# meter.net
KiCad netlist of a schematic drawn in EAGLE
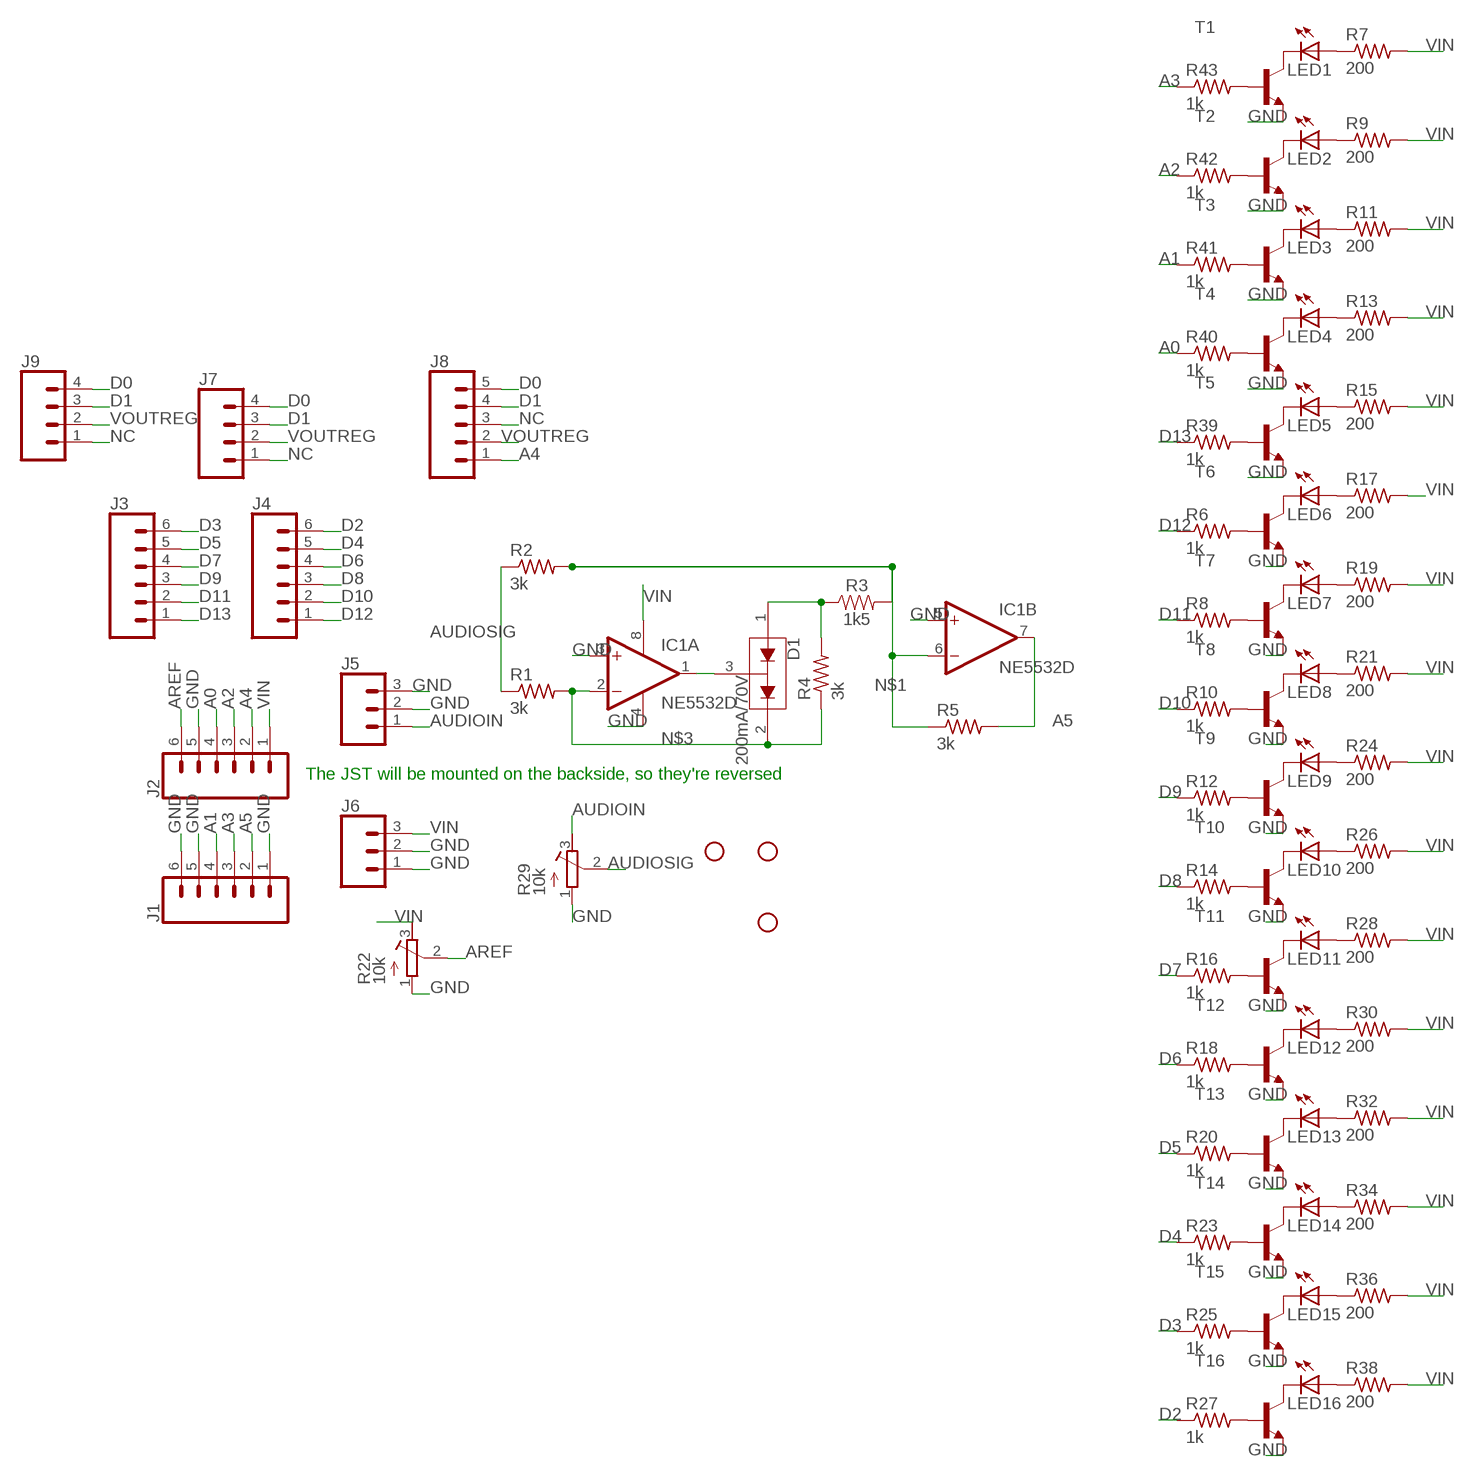
[diagram p0: schematic, sheet 1]

(export (version "E")
  (design (tool "Eeschema 10.0.6"))
  (components
    (comp (ref "D1")
      (value "200mA/70V")
      (footprint "eagle-import:SOT23-3")
      (libsource (lib "eagle-import") (part "BAV99"))
    )
    (comp (ref "H1")
      (value "STAND-OFF")
      (footprint "eagle-import:STAND-OFF")
      (libsource (lib "eagle-import") (part "STAND-OFF"))
    )
    (comp (ref "H2")
      (value "STAND-OFF")
      (footprint "eagle-import:STAND-OFF")
      (libsource (lib "eagle-import") (part "STAND-OFF"))
    )
    (comp (ref "H4")
      (value "STAND-OFF")
      (footprint "eagle-import:STAND-OFF")
      (libsource (lib "eagle-import") (part "STAND-OFF"))
    )
    (comp (ref "IC1")
      (value "NE5532D")
      (footprint "eagle-import:SO08")
      (libsource (lib "eagle-import") (part "NE5532D"))
    )
    (comp (ref "J1")
      (value "CONN_061.27MM")
      (footprint "eagle-import:1X06_1.27MM")
      (libsource (lib "eagle-import") (part "CONN_061.27MM"))
    )
    (comp (ref "J2")
      (value "CONN_061.27MM")
      (footprint "eagle-import:1X06_1.27MM")
      (libsource (lib "eagle-import") (part "CONN_061.27MM"))
    )
    (comp (ref "J3")
      (value "CONN_061.27MM")
      (footprint "eagle-import:1X06_1.27MM")
      (libsource (lib "eagle-import") (part "CONN_061.27MM"))
    )
    (comp (ref "J4")
      (value "CONN_061.27MM")
      (footprint "eagle-import:1X06_1.27MM")
      (libsource (lib "eagle-import") (part "CONN_061.27MM"))
    )
    (comp (ref "J5")
      (value "CONN_03JST-PTH-VERT")
      (footprint "eagle-import:JST-3-PTH-VERT")
      (libsource (lib "eagle-import") (part "CONN_03JST-PTH-VERT"))
    )
    (comp (ref "J6")
      (value "CONN_03JST-PTH-VERT")
      (footprint "eagle-import:JST-3-PTH-VERT")
      (libsource (lib "eagle-import") (part "CONN_03JST-PTH-VERT"))
    )
    (comp (ref "J7")
      (value "CONN_041.27MM")
      (footprint "eagle-import:1X04_1.27MM")
      (libsource (lib "eagle-import") (part "CONN_041.27MM"))
    )
    (comp (ref "J8")
      (value "CONN_05NO_SILK")
      (footprint "eagle-import:1X05_NO_SILK")
      (libsource (lib "eagle-import") (part "CONN_05NO_SILK"))
    )
    (comp (ref "J9")
      (value "CONN_041.27MM")
      (footprint "eagle-import:1X04_1.27MM")
      (libsource (lib "eagle-import") (part "CONN_041.27MM"))
    )
    (comp (ref "LED1")
      (value "LEDCHIP-LED0805")
      (footprint "eagle-import:CHIP-LED0805")
      (libsource (lib "eagle-import") (part "LEDCHIP-LED0805"))
    )
    (comp (ref "LED2")
      (value "LEDCHIP-LED0805")
      (footprint "eagle-import:CHIP-LED0805")
      (libsource (lib "eagle-import") (part "LEDCHIP-LED0805"))
    )
    (comp (ref "LED3")
      (value "LEDCHIP-LED0805")
      (footprint "eagle-import:CHIP-LED0805")
      (libsource (lib "eagle-import") (part "LEDCHIP-LED0805"))
    )
    (comp (ref "LED4")
      (value "LEDCHIP-LED0805")
      (footprint "eagle-import:CHIP-LED0805")
      (libsource (lib "eagle-import") (part "LEDCHIP-LED0805"))
    )
    (comp (ref "LED5")
      (value "LEDCHIP-LED0805")
      (footprint "eagle-import:CHIP-LED0805")
      (libsource (lib "eagle-import") (part "LEDCHIP-LED0805"))
    )
    (comp (ref "LED6")
      (value "LEDCHIP-LED0805")
      (footprint "eagle-import:CHIP-LED0805")
      (libsource (lib "eagle-import") (part "LEDCHIP-LED0805"))
    )
    (comp (ref "LED7")
      (value "LEDCHIP-LED0805")
      (footprint "eagle-import:CHIP-LED0805")
      (libsource (lib "eagle-import") (part "LEDCHIP-LED0805"))
    )
    (comp (ref "LED8")
      (value "LEDCHIP-LED0805")
      (footprint "eagle-import:CHIP-LED0805")
      (libsource (lib "eagle-import") (part "LEDCHIP-LED0805"))
    )
    (comp (ref "LED9")
      (value "LEDCHIP-LED0805")
      (footprint "eagle-import:CHIP-LED0805")
      (libsource (lib "eagle-import") (part "LEDCHIP-LED0805"))
    )
    (comp (ref "LED10")
      (value "LEDCHIP-LED0805")
      (footprint "eagle-import:CHIP-LED0805")
      (libsource (lib "eagle-import") (part "LEDCHIP-LED0805"))
    )
    (comp (ref "LED11")
      (value "LEDCHIP-LED0805")
      (footprint "eagle-import:CHIP-LED0805")
      (libsource (lib "eagle-import") (part "LEDCHIP-LED0805"))
    )
    (comp (ref "LED12")
      (value "LEDCHIP-LED0805")
      (footprint "eagle-import:CHIP-LED0805")
      (libsource (lib "eagle-import") (part "LEDCHIP-LED0805"))
    )
    (comp (ref "LED13")
      (value "LEDCHIP-LED0805")
      (footprint "eagle-import:CHIP-LED0805")
      (libsource (lib "eagle-import") (part "LEDCHIP-LED0805"))
    )
    (comp (ref "LED14")
      (value "LEDCHIP-LED0805")
      (footprint "eagle-import:CHIP-LED0805")
      (libsource (lib "eagle-import") (part "LEDCHIP-LED0805"))
    )
    (comp (ref "LED15")
      (value "LEDCHIP-LED0805")
      (footprint "eagle-import:CHIP-LED0805")
      (libsource (lib "eagle-import") (part "LEDCHIP-LED0805"))
    )
    (comp (ref "LED16")
      (value "LEDCHIP-LED0805")
      (footprint "eagle-import:CHIP-LED0805")
      (libsource (lib "eagle-import") (part "LEDCHIP-LED0805"))
    )
    (comp (ref "R1")
      (value "3k")
      (footprint "eagle-import:R0805")
      (libsource (lib "eagle-import") (part "R-US_R0805"))
    )
    (comp (ref "R2")
      (value "3k")
      (footprint "eagle-import:R0805")
      (libsource (lib "eagle-import") (part "R-US_R0805"))
    )
    (comp (ref "R3")
      (value "1k5")
      (footprint "eagle-import:1206")
      (libsource (lib "eagle-import") (part "RESISTOR1206"))
    )
    (comp (ref "R4")
      (value "3k")
      (footprint "eagle-import:R0805")
      (libsource (lib "eagle-import") (part "R-US_R0805"))
    )
    (comp (ref "R5")
      (value "3k")
      (footprint "eagle-import:R0805")
      (libsource (lib "eagle-import") (part "R-US_R0805"))
    )
    (comp (ref "R6")
      (value "1k")
      (footprint "eagle-import:R0805")
      (libsource (lib "eagle-import") (part "R-US_R0805"))
    )
    (comp (ref "R7")
      (value "200")
      (footprint "eagle-import:R0805")
      (libsource (lib "eagle-import") (part "R-US_R0805"))
    )
    (comp (ref "R8")
      (value "1k")
      (footprint "eagle-import:R0805")
      (libsource (lib "eagle-import") (part "R-US_R0805"))
    )
    (comp (ref "R9")
      (value "200")
      (footprint "eagle-import:R0805")
      (libsource (lib "eagle-import") (part "R-US_R0805"))
    )
    (comp (ref "R10")
      (value "1k")
      (footprint "eagle-import:R0805")
      (libsource (lib "eagle-import") (part "R-US_R0805"))
    )
    (comp (ref "R11")
      (value "200")
      (footprint "eagle-import:R0805")
      (libsource (lib "eagle-import") (part "R-US_R0805"))
    )
    (comp (ref "R12")
      (value "1k")
      (footprint "eagle-import:R0805")
      (libsource (lib "eagle-import") (part "R-US_R0805"))
    )
    (comp (ref "R13")
      (value "200")
      (footprint "eagle-import:R0805")
      (libsource (lib "eagle-import") (part "R-US_R0805"))
    )
    (comp (ref "R14")
      (value "1k")
      (footprint "eagle-import:R0805")
      (libsource (lib "eagle-import") (part "R-US_R0805"))
    )
    (comp (ref "R15")
      (value "200")
      (footprint "eagle-import:R0805")
      (libsource (lib "eagle-import") (part "R-US_R0805"))
    )
    (comp (ref "R16")
      (value "1k")
      (footprint "eagle-import:R0805")
      (libsource (lib "eagle-import") (part "R-US_R0805"))
    )
    (comp (ref "R17")
      (value "200")
      (footprint "eagle-import:R0805")
      (libsource (lib "eagle-import") (part "R-US_R0805"))
    )
    (comp (ref "R18")
      (value "1k")
      (footprint "eagle-import:R0805")
      (libsource (lib "eagle-import") (part "R-US_R0805"))
    )
    (comp (ref "R19")
      (value "200")
      (footprint "eagle-import:R0805")
      (libsource (lib "eagle-import") (part "R-US_R0805"))
    )
    (comp (ref "R20")
      (value "1k")
      (footprint "eagle-import:R0805")
      (libsource (lib "eagle-import") (part "R-US_R0805"))
    )
    (comp (ref "R21")
      (value "200")
      (footprint "eagle-import:R0805")
      (libsource (lib "eagle-import") (part "R-US_R0805"))
    )
    (comp (ref "R22")
      (value "10k")
      (footprint "eagle-import:RTRIM3296Y")
      (libsource (lib "eagle-import") (part "R-TRIMM3296Y"))
    )
    (comp (ref "R23")
      (value "1k")
      (footprint "eagle-import:R0805")
      (libsource (lib "eagle-import") (part "R-US_R0805"))
    )
    (comp (ref "R24")
      (value "200")
      (footprint "eagle-import:R0805")
      (libsource (lib "eagle-import") (part "R-US_R0805"))
    )
    (comp (ref "R25")
      (value "1k")
      (footprint "eagle-import:R0805")
      (libsource (lib "eagle-import") (part "R-US_R0805"))
    )
    (comp (ref "R26")
      (value "200")
      (footprint "eagle-import:R0805")
      (libsource (lib "eagle-import") (part "R-US_R0805"))
    )
    (comp (ref "R27")
      (value "1k")
      (footprint "eagle-import:R0805")
      (libsource (lib "eagle-import") (part "R-US_R0805"))
    )
    (comp (ref "R28")
      (value "200")
      (footprint "eagle-import:R0805")
      (libsource (lib "eagle-import") (part "R-US_R0805"))
    )
    (comp (ref "R29")
      (value "10k")
      (footprint "eagle-import:RTRIM3296Y")
      (libsource (lib "eagle-import") (part "R-TRIMM3296Y"))
    )
    (comp (ref "R30")
      (value "200")
      (footprint "eagle-import:R0805")
      (libsource (lib "eagle-import") (part "R-US_R0805"))
    )
    (comp (ref "R32")
      (value "200")
      (footprint "eagle-import:R0805")
      (libsource (lib "eagle-import") (part "R-US_R0805"))
    )
    (comp (ref "R34")
      (value "200")
      (footprint "eagle-import:R0805")
      (libsource (lib "eagle-import") (part "R-US_R0805"))
    )
    (comp (ref "R36")
      (value "200")
      (footprint "eagle-import:R0805")
      (libsource (lib "eagle-import") (part "R-US_R0805"))
    )
    (comp (ref "R38")
      (value "200")
      (footprint "eagle-import:R0805")
      (libsource (lib "eagle-import") (part "R-US_R0805"))
    )
    (comp (ref "R39")
      (value "1k")
      (footprint "eagle-import:R0805")
      (libsource (lib "eagle-import") (part "R-US_R0805"))
    )
    (comp (ref "R40")
      (value "1k")
      (footprint "eagle-import:R0805")
      (libsource (lib "eagle-import") (part "R-US_R0805"))
    )
    (comp (ref "R41")
      (value "1k")
      (footprint "eagle-import:R0805")
      (libsource (lib "eagle-import") (part "R-US_R0805"))
    )
    (comp (ref "R42")
      (value "1k")
      (footprint "eagle-import:R0805")
      (libsource (lib "eagle-import") (part "R-US_R0805"))
    )
    (comp (ref "R43")
      (value "1k")
      (footprint "eagle-import:R0805")
      (libsource (lib "eagle-import") (part "R-US_R0805"))
    )
    (comp (ref "T1")
      (value "BCX56-NPN-SOT89-BCE")
      (footprint "eagle-import:SOT89-BCE")
      (libsource (lib "eagle-import") (part "-NPN-SOT89-BCEBCX56"))
    )
    (comp (ref "T2")
      (value "BCX56-NPN-SOT89-BCE")
      (footprint "eagle-import:SOT89-BCE")
      (libsource (lib "eagle-import") (part "-NPN-SOT89-BCEBCX56"))
    )
    (comp (ref "T3")
      (value "BCX56-NPN-SOT89-BCE")
      (footprint "eagle-import:SOT89-BCE")
      (libsource (lib "eagle-import") (part "-NPN-SOT89-BCEBCX56"))
    )
    (comp (ref "T4")
      (value "BCX56-NPN-SOT89-BCE")
      (footprint "eagle-import:SOT89-BCE")
      (libsource (lib "eagle-import") (part "-NPN-SOT89-BCEBCX56"))
    )
    (comp (ref "T5")
      (value "BCX56-NPN-SOT89-BCE")
      (footprint "eagle-import:SOT89-BCE")
      (libsource (lib "eagle-import") (part "-NPN-SOT89-BCEBCX56"))
    )
    (comp (ref "T6")
      (value "BCX56-NPN-SOT89-BCE")
      (footprint "eagle-import:SOT89-BCE")
      (libsource (lib "eagle-import") (part "-NPN-SOT89-BCEBCX56"))
    )
    (comp (ref "T7")
      (value "BCX56-NPN-SOT89-BCE")
      (footprint "eagle-import:SOT89-BCE")
      (libsource (lib "eagle-import") (part "-NPN-SOT89-BCEBCX56"))
    )
    (comp (ref "T8")
      (value "BCX56-NPN-SOT89-BCE")
      (footprint "eagle-import:SOT89-BCE")
      (libsource (lib "eagle-import") (part "-NPN-SOT89-BCEBCX56"))
    )
    (comp (ref "T9")
      (value "BCX56-NPN-SOT89-BCE")
      (footprint "eagle-import:SOT89-BCE")
      (libsource (lib "eagle-import") (part "-NPN-SOT89-BCEBCX56"))
    )
    (comp (ref "T10")
      (value "BCX56-NPN-SOT89-BCE")
      (footprint "eagle-import:SOT89-BCE")
      (libsource (lib "eagle-import") (part "-NPN-SOT89-BCEBCX56"))
    )
    (comp (ref "T11")
      (value "BCX56-NPN-SOT89-BCE")
      (footprint "eagle-import:SOT89-BCE")
      (libsource (lib "eagle-import") (part "-NPN-SOT89-BCEBCX56"))
    )
    (comp (ref "T12")
      (value "BCX56-NPN-SOT89-BCE")
      (footprint "eagle-import:SOT89-BCE")
      (libsource (lib "eagle-import") (part "-NPN-SOT89-BCEBCX56"))
    )
    (comp (ref "T13")
      (value "BCX56-NPN-SOT89-BCE")
      (footprint "eagle-import:SOT89-BCE")
      (libsource (lib "eagle-import") (part "-NPN-SOT89-BCEBCX56"))
    )
    (comp (ref "T14")
      (value "BCX56-NPN-SOT89-BCE")
      (footprint "eagle-import:SOT89-BCE")
      (libsource (lib "eagle-import") (part "-NPN-SOT89-BCEBCX56"))
    )
    (comp (ref "T15")
      (value "BCX56-NPN-SOT89-BCE")
      (footprint "eagle-import:SOT89-BCE")
      (libsource (lib "eagle-import") (part "-NPN-SOT89-BCEBCX56"))
    )
    (comp (ref "T16")
      (value "BCX56-NPN-SOT89-BCE")
      (footprint "eagle-import:SOT89-BCE")
      (libsource (lib "eagle-import") (part "-NPN-SOT89-BCEBCX56"))
    )
  )
  (nets
    (net (code "1") (name "/A0") (class "Default")
      (node (ref "J2") (pin "4") (pinfunction "4_4") (pintype "passive"))
      (node (ref "R40") (pin "1") (pinfunction "1_1") (pintype "passive"))
    )
    (net (code "2") (name "/A1") (class "Default")
      (node (ref "J1") (pin "4") (pinfunction "4_4") (pintype "passive"))
      (node (ref "R41") (pin "1") (pinfunction "1_1") (pintype "passive"))
    )
    (net (code "3") (name "/A2") (class "Default")
      (node (ref "J2") (pin "3") (pinfunction "3_3") (pintype "passive"))
      (node (ref "R42") (pin "1") (pinfunction "1_1") (pintype "passive"))
    )
    (net (code "4") (name "/A3") (class "Default")
      (node (ref "J1") (pin "3") (pinfunction "3_3") (pintype "passive"))
      (node (ref "R43") (pin "1") (pinfunction "1_1") (pintype "passive"))
    )
    (net (code "5") (name "/A4") (class "Default")
      (node (ref "J2") (pin "2") (pinfunction "2_2") (pintype "passive"))
      (node (ref "J8") (pin "1") (pinfunction "1_1") (pintype "passive"))
    )
    (net (code "6") (name "/A5") (class "Default")
      (node (ref "IC1") (pin "7") (pinfunction "OUT_7") (pintype "output"))
      (node (ref "J1") (pin "2") (pinfunction "2_2") (pintype "passive"))
      (node (ref "R5") (pin "2") (pinfunction "2_2") (pintype "passive"))
    )
    (net (code "7") (name "/AREF") (class "Default")
      (node (ref "J2") (pin "6") (pinfunction "6_6") (pintype "passive"))
      (node (ref "R22") (pin "2") (pinfunction "S_2") (pintype "passive"))
    )
    (net (code "8") (name "/AUDIOIN") (class "Default")
      (node (ref "J5") (pin "1") (pinfunction "1_1") (pintype "passive"))
      (node (ref "R29") (pin "3") (pinfunction "E_3") (pintype "passive"))
    )
    (net (code "9") (name "/AUDIOSIG") (class "Default")
      (node (ref "R1") (pin "1") (pinfunction "1_1") (pintype "passive"))
      (node (ref "R2") (pin "1") (pinfunction "1_1") (pintype "passive"))
      (node (ref "R29") (pin "2") (pinfunction "S_2") (pintype "passive"))
    )
    (net (code "10") (name "/D0") (class "Default")
      (node (ref "J7") (pin "4") (pinfunction "4_4") (pintype "passive"))
      (node (ref "J8") (pin "5") (pinfunction "5_5") (pintype "passive"))
      (node (ref "J9") (pin "4") (pinfunction "4_4") (pintype "passive"))
    )
    (net (code "11") (name "/D1") (class "Default")
      (node (ref "J7") (pin "3") (pinfunction "3_3") (pintype "passive"))
      (node (ref "J8") (pin "4") (pinfunction "4_4") (pintype "passive"))
      (node (ref "J9") (pin "3") (pinfunction "3_3") (pintype "passive"))
    )
    (net (code "12") (name "/D2") (class "Default")
      (node (ref "J4") (pin "6") (pinfunction "6_6") (pintype "passive"))
      (node (ref "R27") (pin "1") (pinfunction "1_1") (pintype "passive"))
    )
    (net (code "13") (name "/D3") (class "Default")
      (node (ref "J3") (pin "6") (pinfunction "6_6") (pintype "passive"))
      (node (ref "R25") (pin "1") (pinfunction "1_1") (pintype "passive"))
    )
    (net (code "14") (name "/D4") (class "Default")
      (node (ref "J4") (pin "5") (pinfunction "5_5") (pintype "passive"))
      (node (ref "R23") (pin "1") (pinfunction "1_1") (pintype "passive"))
    )
    (net (code "15") (name "/D5") (class "Default")
      (node (ref "J3") (pin "5") (pinfunction "5_5") (pintype "passive"))
      (node (ref "R20") (pin "1") (pinfunction "1_1") (pintype "passive"))
    )
    (net (code "16") (name "/D6") (class "Default")
      (node (ref "J4") (pin "4") (pinfunction "4_4") (pintype "passive"))
      (node (ref "R18") (pin "1") (pinfunction "1_1") (pintype "passive"))
    )
    (net (code "17") (name "/D7") (class "Default")
      (node (ref "J3") (pin "4") (pinfunction "4_4") (pintype "passive"))
      (node (ref "R16") (pin "1") (pinfunction "1_1") (pintype "passive"))
    )
    (net (code "18") (name "/D8") (class "Default")
      (node (ref "J4") (pin "3") (pinfunction "3_3") (pintype "passive"))
      (node (ref "R14") (pin "1") (pinfunction "1_1") (pintype "passive"))
    )
    (net (code "19") (name "/D9") (class "Default")
      (node (ref "J3") (pin "3") (pinfunction "3_3") (pintype "passive"))
      (node (ref "R12") (pin "1") (pinfunction "1_1") (pintype "passive"))
    )
    (net (code "20") (name "/D10") (class "Default")
      (node (ref "J4") (pin "2") (pinfunction "2_2") (pintype "passive"))
      (node (ref "R10") (pin "1") (pinfunction "1_1") (pintype "passive"))
    )
    (net (code "21") (name "/D11") (class "Default")
      (node (ref "J3") (pin "2") (pinfunction "2_2") (pintype "passive"))
      (node (ref "R8") (pin "1") (pinfunction "1_1") (pintype "passive"))
    )
    (net (code "22") (name "/D12") (class "Default")
      (node (ref "J4") (pin "1") (pinfunction "1_1") (pintype "passive"))
      (node (ref "R6") (pin "1") (pinfunction "1_1") (pintype "passive"))
    )
    (net (code "23") (name "/D13") (class "Default")
      (node (ref "J3") (pin "1") (pinfunction "1_1") (pintype "passive"))
      (node (ref "R39") (pin "1") (pinfunction "1_1") (pintype "passive"))
    )
    (net (code "24") (name "/GND") (class "Default")
      (node (ref "IC1") (pin "3") (pinfunction "+IN_3") (pintype "input"))
      (node (ref "IC1") (pin "4") (pinfunction "V-_4") (pintype "power_in"))
      (node (ref "IC1") (pin "5") (pinfunction "+IN_5") (pintype "input"))
      (node (ref "J1") (pin "1") (pinfunction "1_1") (pintype "passive"))
      (node (ref "J1") (pin "5") (pinfunction "5_5") (pintype "passive"))
      (node (ref "J1") (pin "6") (pinfunction "6_6") (pintype "passive"))
      (node (ref "J2") (pin "5") (pinfunction "5_5") (pintype "passive"))
      (node (ref "J5") (pin "2") (pinfunction "2_2") (pintype "passive"))
      (node (ref "J5") (pin "3") (pinfunction "3_3") (pintype "passive"))
      (node (ref "J6") (pin "1") (pinfunction "1_1") (pintype "passive"))
      (node (ref "J6") (pin "2") (pinfunction "2_2") (pintype "passive"))
      (node (ref "R22") (pin "1") (pinfunction "A_1") (pintype "passive"))
      (node (ref "R29") (pin "1") (pinfunction "A_1") (pintype "passive"))
      (node (ref "T1") (pin "E") (pinfunction "E_E") (pintype "passive"))
      (node (ref "T10") (pin "E") (pinfunction "E_E") (pintype "passive"))
      (node (ref "T11") (pin "E") (pinfunction "E_E") (pintype "passive"))
      (node (ref "T12") (pin "E") (pinfunction "E_E") (pintype "passive"))
      (node (ref "T13") (pin "E") (pinfunction "E_E") (pintype "passive"))
      (node (ref "T14") (pin "E") (pinfunction "E_E") (pintype "passive"))
      (node (ref "T15") (pin "E") (pinfunction "E_E") (pintype "passive"))
      (node (ref "T16") (pin "E") (pinfunction "E_E") (pintype "passive"))
      (node (ref "T2") (pin "E") (pinfunction "E_E") (pintype "passive"))
      (node (ref "T3") (pin "E") (pinfunction "E_E") (pintype "passive"))
      (node (ref "T4") (pin "E") (pinfunction "E_E") (pintype "passive"))
      (node (ref "T5") (pin "E") (pinfunction "E_E") (pintype "passive"))
      (node (ref "T6") (pin "E") (pinfunction "E_E") (pintype "passive"))
      (node (ref "T7") (pin "E") (pinfunction "E_E") (pintype "passive"))
      (node (ref "T8") (pin "E") (pinfunction "E_E") (pintype "passive"))
      (node (ref "T9") (pin "E") (pinfunction "E_E") (pintype "passive"))
    )
    (net (code "25") (name "/N$1") (class "Default")
      (node (ref "IC1") (pin "6") (pinfunction "-IN_6") (pintype "input"))
      (node (ref "R2") (pin "2") (pinfunction "2_2") (pintype "passive"))
      (node (ref "R3") (pin "2") (pinfunction "2_2") (pintype "passive"))
      (node (ref "R5") (pin "1") (pinfunction "1_1") (pintype "passive"))
    )
    (net (code "26") (name "/N$3") (class "Default")
      (node (ref "D1") (pin "2") (pinfunction "C2_2") (pintype "bidirectional"))
      (node (ref "IC1") (pin "2") (pinfunction "-IN_2") (pintype "input"))
      (node (ref "R1") (pin "2") (pinfunction "2_2") (pintype "passive"))
      (node (ref "R4") (pin "1") (pinfunction "1_1") (pintype "passive"))
    )
    (net (code "27") (name "/NC") (class "Default")
      (node (ref "J7") (pin "1") (pinfunction "1_1") (pintype "passive"))
      (node (ref "J8") (pin "3") (pinfunction "3_3") (pintype "passive"))
      (node (ref "J9") (pin "1") (pinfunction "1_1") (pintype "passive"))
    )
    (net (code "28") (name "/VIN") (class "Default")
      (node (ref "IC1") (pin "8") (pinfunction "V+_8") (pintype "power_in"))
      (node (ref "J2") (pin "1") (pinfunction "1_1") (pintype "passive"))
      (node (ref "J6") (pin "3") (pinfunction "3_3") (pintype "passive"))
      (node (ref "R11") (pin "2") (pinfunction "2_2") (pintype "passive"))
      (node (ref "R13") (pin "2") (pinfunction "2_2") (pintype "passive"))
      (node (ref "R15") (pin "2") (pinfunction "2_2") (pintype "passive"))
      (node (ref "R17") (pin "2") (pinfunction "2_2") (pintype "passive"))
      (node (ref "R19") (pin "2") (pinfunction "2_2") (pintype "passive"))
      (node (ref "R21") (pin "2") (pinfunction "2_2") (pintype "passive"))
      (node (ref "R22") (pin "3") (pinfunction "E_3") (pintype "passive"))
      (node (ref "R24") (pin "2") (pinfunction "2_2") (pintype "passive"))
      (node (ref "R26") (pin "2") (pinfunction "2_2") (pintype "passive"))
      (node (ref "R28") (pin "2") (pinfunction "2_2") (pintype "passive"))
      (node (ref "R30") (pin "2") (pinfunction "2_2") (pintype "passive"))
      (node (ref "R32") (pin "2") (pinfunction "2_2") (pintype "passive"))
      (node (ref "R34") (pin "2") (pinfunction "2_2") (pintype "passive"))
      (node (ref "R36") (pin "2") (pinfunction "2_2") (pintype "passive"))
      (node (ref "R38") (pin "2") (pinfunction "2_2") (pintype "passive"))
      (node (ref "R7") (pin "2") (pinfunction "2_2") (pintype "passive"))
      (node (ref "R9") (pin "2") (pinfunction "2_2") (pintype "passive"))
    )
    (net (code "29") (name "/VOUTREG") (class "Default")
      (node (ref "J7") (pin "2") (pinfunction "2_2") (pintype "passive"))
      (node (ref "J8") (pin "2") (pinfunction "2_2") (pintype "passive"))
      (node (ref "J9") (pin "2") (pinfunction "2_2") (pintype "passive"))
    )
    (net (code "30") (name "Net-(D1-A1)") (class "Default")
      (node (ref "D1") (pin "1") (pinfunction "A1_1") (pintype "bidirectional"))
      (node (ref "R3") (pin "1") (pinfunction "1_1") (pintype "passive"))
      (node (ref "R4") (pin "2") (pinfunction "2_2") (pintype "passive"))
    )
    (net (code "31") (name "Net-(D1-COM)") (class "Default")
      (node (ref "D1") (pin "3") (pinfunction "COM_3") (pintype "bidirectional"))
      (node (ref "IC1") (pin "1") (pinfunction "OUT_1") (pintype "output"))
    )
    (net (code "32") (name "Net-(LED1-PadA)") (class "Default")
      (node (ref "LED1") (pin "A") (pinfunction "A_A") (pintype "passive"))
      (node (ref "R7") (pin "1") (pinfunction "1_1") (pintype "passive"))
    )
    (net (code "33") (name "Net-(LED1-PadC)") (class "Default")
      (node (ref "LED1") (pin "C") (pinfunction "C_C") (pintype "passive"))
      (node (ref "T1") (pin "C") (pinfunction "C_C") (pintype "passive"))
    )
    (net (code "34") (name "Net-(LED2-PadA)") (class "Default")
      (node (ref "LED2") (pin "A") (pinfunction "A_A") (pintype "passive"))
      (node (ref "R9") (pin "1") (pinfunction "1_1") (pintype "passive"))
    )
    (net (code "35") (name "Net-(LED2-PadC)") (class "Default")
      (node (ref "LED2") (pin "C") (pinfunction "C_C") (pintype "passive"))
      (node (ref "T2") (pin "C") (pinfunction "C_C") (pintype "passive"))
    )
    (net (code "36") (name "Net-(LED3-PadA)") (class "Default")
      (node (ref "LED3") (pin "A") (pinfunction "A_A") (pintype "passive"))
      (node (ref "R11") (pin "1") (pinfunction "1_1") (pintype "passive"))
    )
    (net (code "37") (name "Net-(LED3-PadC)") (class "Default")
      (node (ref "LED3") (pin "C") (pinfunction "C_C") (pintype "passive"))
      (node (ref "T3") (pin "C") (pinfunction "C_C") (pintype "passive"))
    )
    (net (code "38") (name "Net-(LED4-PadA)") (class "Default")
      (node (ref "LED4") (pin "A") (pinfunction "A_A") (pintype "passive"))
      (node (ref "R13") (pin "1") (pinfunction "1_1") (pintype "passive"))
    )
    (net (code "39") (name "Net-(LED4-PadC)") (class "Default")
      (node (ref "LED4") (pin "C") (pinfunction "C_C") (pintype "passive"))
      (node (ref "T4") (pin "C") (pinfunction "C_C") (pintype "passive"))
    )
    (net (code "40") (name "Net-(LED5-PadA)") (class "Default")
      (node (ref "LED5") (pin "A") (pinfunction "A_A") (pintype "passive"))
      (node (ref "R15") (pin "1") (pinfunction "1_1") (pintype "passive"))
    )
    (net (code "41") (name "Net-(LED5-PadC)") (class "Default")
      (node (ref "LED5") (pin "C") (pinfunction "C_C") (pintype "passive"))
      (node (ref "T5") (pin "C") (pinfunction "C_C") (pintype "passive"))
    )
    (net (code "42") (name "Net-(LED6-PadA)") (class "Default")
      (node (ref "LED6") (pin "A") (pinfunction "A_A") (pintype "passive"))
      (node (ref "R17") (pin "1") (pinfunction "1_1") (pintype "passive"))
    )
    (net (code "43") (name "Net-(LED6-PadC)") (class "Default")
      (node (ref "LED6") (pin "C") (pinfunction "C_C") (pintype "passive"))
      (node (ref "T6") (pin "C") (pinfunction "C_C") (pintype "passive"))
    )
    (net (code "44") (name "Net-(LED7-PadA)") (class "Default")
      (node (ref "LED7") (pin "A") (pinfunction "A_A") (pintype "passive"))
      (node (ref "R19") (pin "1") (pinfunction "1_1") (pintype "passive"))
    )
    (net (code "45") (name "Net-(LED7-PadC)") (class "Default")
      (node (ref "LED7") (pin "C") (pinfunction "C_C") (pintype "passive"))
      (node (ref "T7") (pin "C") (pinfunction "C_C") (pintype "passive"))
    )
    (net (code "46") (name "Net-(LED8-PadA)") (class "Default")
      (node (ref "LED8") (pin "A") (pinfunction "A_A") (pintype "passive"))
      (node (ref "R21") (pin "1") (pinfunction "1_1") (pintype "passive"))
    )
    (net (code "47") (name "Net-(LED8-PadC)") (class "Default")
      (node (ref "LED8") (pin "C") (pinfunction "C_C") (pintype "passive"))
      (node (ref "T8") (pin "C") (pinfunction "C_C") (pintype "passive"))
    )
    (net (code "48") (name "Net-(LED9-PadA)") (class "Default")
      (node (ref "LED9") (pin "A") (pinfunction "A_A") (pintype "passive"))
      (node (ref "R24") (pin "1") (pinfunction "1_1") (pintype "passive"))
    )
    (net (code "49") (name "Net-(LED9-PadC)") (class "Default")
      (node (ref "LED9") (pin "C") (pinfunction "C_C") (pintype "passive"))
      (node (ref "T9") (pin "C") (pinfunction "C_C") (pintype "passive"))
    )
    (net (code "50") (name "Net-(LED10-PadA)") (class "Default")
      (node (ref "LED10") (pin "A") (pinfunction "A_A") (pintype "passive"))
      (node (ref "R26") (pin "1") (pinfunction "1_1") (pintype "passive"))
    )
    (net (code "51") (name "Net-(LED10-PadC)") (class "Default")
      (node (ref "LED10") (pin "C") (pinfunction "C_C") (pintype "passive"))
      (node (ref "T10") (pin "C") (pinfunction "C_C") (pintype "passive"))
    )
    (net (code "52") (name "Net-(LED11-PadA)") (class "Default")
      (node (ref "LED11") (pin "A") (pinfunction "A_A") (pintype "passive"))
      (node (ref "R28") (pin "1") (pinfunction "1_1") (pintype "passive"))
    )
    (net (code "53") (name "Net-(LED11-PadC)") (class "Default")
      (node (ref "LED11") (pin "C") (pinfunction "C_C") (pintype "passive"))
      (node (ref "T11") (pin "C") (pinfunction "C_C") (pintype "passive"))
    )
    (net (code "54") (name "Net-(LED12-PadA)") (class "Default")
      (node (ref "LED12") (pin "A") (pinfunction "A_A") (pintype "passive"))
      (node (ref "R30") (pin "1") (pinfunction "1_1") (pintype "passive"))
    )
    (net (code "55") (name "Net-(LED12-PadC)") (class "Default")
      (node (ref "LED12") (pin "C") (pinfunction "C_C") (pintype "passive"))
      (node (ref "T12") (pin "C") (pinfunction "C_C") (pintype "passive"))
    )
    (net (code "56") (name "Net-(LED13-PadA)") (class "Default")
      (node (ref "LED13") (pin "A") (pinfunction "A_A") (pintype "passive"))
      (node (ref "R32") (pin "1") (pinfunction "1_1") (pintype "passive"))
    )
    (net (code "57") (name "Net-(LED13-PadC)") (class "Default")
      (node (ref "LED13") (pin "C") (pinfunction "C_C") (pintype "passive"))
      (node (ref "T13") (pin "C") (pinfunction "C_C") (pintype "passive"))
    )
    (net (code "58") (name "Net-(LED14-PadA)") (class "Default")
      (node (ref "LED14") (pin "A") (pinfunction "A_A") (pintype "passive"))
      (node (ref "R34") (pin "1") (pinfunction "1_1") (pintype "passive"))
    )
    (net (code "59") (name "Net-(LED14-PadC)") (class "Default")
      (node (ref "LED14") (pin "C") (pinfunction "C_C") (pintype "passive"))
      (node (ref "T14") (pin "C") (pinfunction "C_C") (pintype "passive"))
    )
    (net (code "60") (name "Net-(LED15-PadA)") (class "Default")
      (node (ref "LED15") (pin "A") (pinfunction "A_A") (pintype "passive"))
      (node (ref "R36") (pin "1") (pinfunction "1_1") (pintype "passive"))
    )
    (net (code "61") (name "Net-(LED15-PadC)") (class "Default")
      (node (ref "LED15") (pin "C") (pinfunction "C_C") (pintype "passive"))
      (node (ref "T15") (pin "C") (pinfunction "C_C") (pintype "passive"))
    )
    (net (code "62") (name "Net-(LED16-PadA)") (class "Default")
      (node (ref "LED16") (pin "A") (pinfunction "A_A") (pintype "passive"))
      (node (ref "R38") (pin "1") (pinfunction "1_1") (pintype "passive"))
    )
    (net (code "63") (name "Net-(LED16-PadC)") (class "Default")
      (node (ref "LED16") (pin "C") (pinfunction "C_C") (pintype "passive"))
      (node (ref "T16") (pin "C") (pinfunction "C_C") (pintype "passive"))
    )
    (net (code "64") (name "Net-(R6-Pad2)") (class "Default")
      (node (ref "R6") (pin "2") (pinfunction "2_2") (pintype "passive"))
      (node (ref "T6") (pin "B") (pinfunction "B_B") (pintype "passive"))
    )
    (net (code "65") (name "Net-(R8-Pad2)") (class "Default")
      (node (ref "R8") (pin "2") (pinfunction "2_2") (pintype "passive"))
      (node (ref "T7") (pin "B") (pinfunction "B_B") (pintype "passive"))
    )
    (net (code "66") (name "Net-(R10-Pad2)") (class "Default")
      (node (ref "R10") (pin "2") (pinfunction "2_2") (pintype "passive"))
      (node (ref "T8") (pin "B") (pinfunction "B_B") (pintype "passive"))
    )
    (net (code "67") (name "Net-(R12-Pad2)") (class "Default")
      (node (ref "R12") (pin "2") (pinfunction "2_2") (pintype "passive"))
      (node (ref "T9") (pin "B") (pinfunction "B_B") (pintype "passive"))
    )
    (net (code "68") (name "Net-(R14-Pad2)") (class "Default")
      (node (ref "R14") (pin "2") (pinfunction "2_2") (pintype "passive"))
      (node (ref "T10") (pin "B") (pinfunction "B_B") (pintype "passive"))
    )
    (net (code "69") (name "Net-(R16-Pad2)") (class "Default")
      (node (ref "R16") (pin "2") (pinfunction "2_2") (pintype "passive"))
      (node (ref "T11") (pin "B") (pinfunction "B_B") (pintype "passive"))
    )
    (net (code "70") (name "Net-(R18-Pad2)") (class "Default")
      (node (ref "R18") (pin "2") (pinfunction "2_2") (pintype "passive"))
      (node (ref "T12") (pin "B") (pinfunction "B_B") (pintype "passive"))
    )
    (net (code "71") (name "Net-(R20-Pad2)") (class "Default")
      (node (ref "R20") (pin "2") (pinfunction "2_2") (pintype "passive"))
      (node (ref "T13") (pin "B") (pinfunction "B_B") (pintype "passive"))
    )
    (net (code "72") (name "Net-(R23-Pad2)") (class "Default")
      (node (ref "R23") (pin "2") (pinfunction "2_2") (pintype "passive"))
      (node (ref "T14") (pin "B") (pinfunction "B_B") (pintype "passive"))
    )
    (net (code "73") (name "Net-(R25-Pad2)") (class "Default")
      (node (ref "R25") (pin "2") (pinfunction "2_2") (pintype "passive"))
      (node (ref "T15") (pin "B") (pinfunction "B_B") (pintype "passive"))
    )
    (net (code "74") (name "Net-(R27-Pad2)") (class "Default")
      (node (ref "R27") (pin "2") (pinfunction "2_2") (pintype "passive"))
      (node (ref "T16") (pin "B") (pinfunction "B_B") (pintype "passive"))
    )
    (net (code "75") (name "Net-(R39-Pad2)") (class "Default")
      (node (ref "R39") (pin "2") (pinfunction "2_2") (pintype "passive"))
      (node (ref "T5") (pin "B") (pinfunction "B_B") (pintype "passive"))
    )
    (net (code "76") (name "Net-(R40-Pad2)") (class "Default")
      (node (ref "R40") (pin "2") (pinfunction "2_2") (pintype "passive"))
      (node (ref "T4") (pin "B") (pinfunction "B_B") (pintype "passive"))
    )
    (net (code "77") (name "Net-(R41-Pad2)") (class "Default")
      (node (ref "R41") (pin "2") (pinfunction "2_2") (pintype "passive"))
      (node (ref "T3") (pin "B") (pinfunction "B_B") (pintype "passive"))
    )
    (net (code "78") (name "Net-(R42-Pad2)") (class "Default")
      (node (ref "R42") (pin "2") (pinfunction "2_2") (pintype "passive"))
      (node (ref "T2") (pin "B") (pinfunction "B_B") (pintype "passive"))
    )
    (net (code "79") (name "Net-(R43-Pad2)") (class "Default")
      (node (ref "R43") (pin "2") (pinfunction "2_2") (pintype "passive"))
      (node (ref "T1") (pin "B") (pinfunction "B_B") (pintype "passive"))
    )
  )
)
